# front_gap_sensor.net
KiCad netlist of a schematic drawn in EAGLE
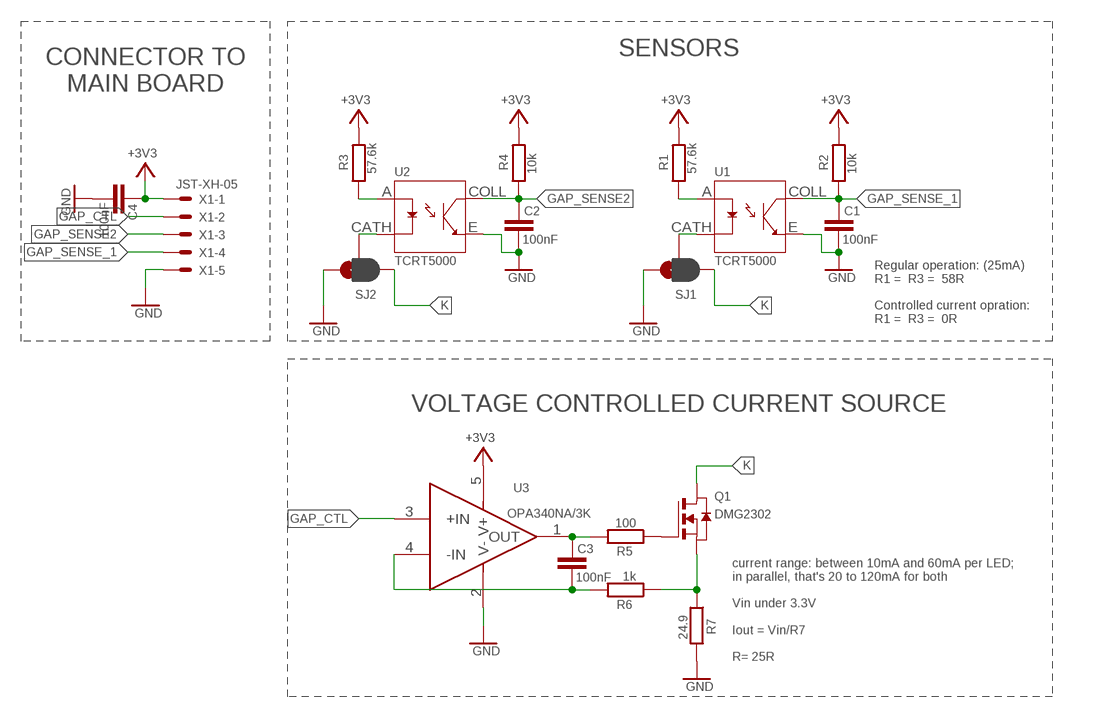
[diagram p0: schematic, sheet 1]

(export (version "E")
  (design (tool "Eeschema 10.0.6"))
  (components
    (comp (ref "C1")
      (value "100nF")
      (footprint "eagle-import:C0402")
      (libsource (lib "eagle-import") (part "C-EUC0402"))
    )
    (comp (ref "C2")
      (value "100nF")
      (footprint "eagle-import:C0402")
      (libsource (lib "eagle-import") (part "C-EUC0402"))
    )
    (comp (ref "C3")
      (value "100nF")
      (footprint "eagle-import:C0402")
      (libsource (lib "eagle-import") (part "C-EUC0402"))
    )
    (comp (ref "C4")
      (value "100nF")
      (footprint "eagle-import:C0402")
      (libsource (lib "eagle-import") (part "C-EUC0402"))
    )
    (comp (ref "Q1")
      (value "DMG2302")
      (footprint "eagle-import:SOT-23")
      (libsource (lib "eagle-import") (part "NMOS-SOT23"))
    )
    (comp (ref "R1")
      (value "57.6k")
      (footprint "eagle-import:R0402")
      (libsource (lib "eagle-import") (part "R-EU_R0402"))
    )
    (comp (ref "R2")
      (value "10k")
      (footprint "eagle-import:R0402")
      (libsource (lib "eagle-import") (part "R-EU_R0402"))
    )
    (comp (ref "R3")
      (value "57.6k")
      (footprint "eagle-import:R0402")
      (libsource (lib "eagle-import") (part "R-EU_R0402"))
    )
    (comp (ref "R4")
      (value "10k")
      (footprint "eagle-import:R0402")
      (libsource (lib "eagle-import") (part "R-EU_R0402"))
    )
    (comp (ref "R5")
      (value "100")
      (footprint "eagle-import:R0402")
      (libsource (lib "eagle-import") (part "R-EU_R0402"))
    )
    (comp (ref "R6")
      (value "1k")
      (footprint "eagle-import:R0402")
      (libsource (lib "eagle-import") (part "R-EU_R0402"))
    )
    (comp (ref "R7")
      (value "24.9")
      (footprint "eagle-import:R0402")
      (libsource (lib "eagle-import") (part "R-EU_R0402"))
    )
    (comp (ref "SJ1")
      (value "SPARKFUN-PASSIVES_JUMPER_PAD-3-1&2_NC_BY_PASTE")
      (footprint "eagle-import:SPARKFUN-PASSIVES_PAD-HUMPER-3-1&2_NC_BY_PASTE_YES_SILK_FULL_BOX")
      (libsource (lib "eagle-import") (part "SPARKFUN-PASSIVES_JUMPER_PAD-3-1&2_NC_BY_PASTE"))
    )
    (comp (ref "SJ2")
      (value "SPARKFUN-PASSIVES_JUMPER_PAD-3-1&2_NC_BY_PASTE")
      (footprint "eagle-import:SPARKFUN-PASSIVES_PAD-HUMPER-3-1&2_NC_BY_PASTE_YES_SILK_FULL_BOX")
      (libsource (lib "eagle-import") (part "SPARKFUN-PASSIVES_JUMPER_PAD-3-1&2_NC_BY_PASTE"))
    )
    (comp (ref "U1")
      (value "TCRT5000")
      (footprint "eagle-import:OPTO_TCRT5000")
      (fields (field (name "MF") "Vishay"))
      (libsource (lib "eagle-import") (part "TCRT5000"))
    )
    (comp (ref "U2")
      (value "TCRT5000")
      (footprint "eagle-import:OPTO_TCRT5000")
      (fields (field (name "MF") "Vishay"))
      (libsource (lib "eagle-import") (part "TCRT5000"))
    )
    (comp (ref "U3")
      (value "OPA340NA/3K")
      (footprint "eagle-import:SOT95P280X145-5N")
      (fields (field (name "MF") "Texas Instruments"))
      (libsource (lib "eagle-import") (part "OPA340NA/3K"))
    )
    (comp (ref "X1")
      (value "JST-XH-05")
      (footprint "eagle-import:JST-XH-05-PACKAGE-ROUND-PAD")
      (libsource (lib "eagle-import") (part "JST-XH-05-PIN-ROUND-PAD"))
    )
  )
  (nets
    (net (code "1") (name "+3V3") (class "Default")
      (node (ref "C4") (pin "2") (pinfunction "2_2") (pintype "passive"))
      (node (ref "R1") (pin "2") (pinfunction "2_2") (pintype "passive"))
      (node (ref "R2") (pin "2") (pinfunction "2_2") (pintype "passive"))
      (node (ref "R3") (pin "2") (pinfunction "2_2") (pintype "passive"))
      (node (ref "R4") (pin "2") (pinfunction "2_2") (pintype "passive"))
      (node (ref "U3") (pin "5") (pinfunction "V+_5") (pintype "power_in"))
      (node (ref "X1") (pin "1") (pinfunction "S_1") (pintype "passive"))
    )
    (net (code "2") (name "GAP_CTL") (class "Default")
      (node (ref "U3") (pin "3") (pinfunction "+IN_3") (pintype "input"))
      (node (ref "X1") (pin "2") (pinfunction "S_2") (pintype "passive"))
    )
    (net (code "3") (name "GAP_SENSE2") (class "Default")
      (node (ref "C2") (pin "2") (pinfunction "2_2") (pintype "passive"))
      (node (ref "R4") (pin "1") (pinfunction "1_1") (pintype "passive"))
      (node (ref "U2") (pin "COLL") (pinfunction "COLL_COLL") (pintype "passive"))
      (node (ref "X1") (pin "3") (pinfunction "S_3") (pintype "passive"))
    )
    (net (code "4") (name "GAP_SENSE_1") (class "Default")
      (node (ref "C1") (pin "2") (pinfunction "2_2") (pintype "passive"))
      (node (ref "R2") (pin "1") (pinfunction "1_1") (pintype "passive"))
      (node (ref "U1") (pin "COLL") (pinfunction "COLL_COLL") (pintype "passive"))
      (node (ref "X1") (pin "4") (pinfunction "S_4") (pintype "passive"))
    )
    (net (code "5") (name "GND") (class "Default")
      (node (ref "C1") (pin "1") (pinfunction "1_1") (pintype "passive"))
      (node (ref "C2") (pin "1") (pinfunction "1_1") (pintype "passive"))
      (node (ref "C4") (pin "1") (pinfunction "1_1") (pintype "passive"))
      (node (ref "R7") (pin "2") (pinfunction "2_2") (pintype "passive"))
      (node (ref "SJ1") (pin "3") (pinfunction "3_3") (pintype "passive"))
      (node (ref "SJ2") (pin "3") (pinfunction "3_3") (pintype "passive"))
      (node (ref "U1") (pin "E") (pinfunction "E_E") (pintype "passive"))
      (node (ref "U2") (pin "E") (pinfunction "E_E") (pintype "passive"))
      (node (ref "U3") (pin "2") (pinfunction "V-_2") (pintype "power_in"))
      (node (ref "X1") (pin "5") (pinfunction "S_5") (pintype "passive"))
    )
    (net (code "6") (name "K") (class "Default")
      (node (ref "Q1") (pin "D") (pinfunction "D_D") (pintype "passive"))
      (node (ref "SJ1") (pin "1") (pinfunction "1_1") (pintype "passive"))
      (node (ref "SJ2") (pin "1") (pinfunction "1_1") (pintype "passive"))
    )
    (net (code "7") (name "Net-(Q1-PadG)") (class "Default")
      (node (ref "Q1") (pin "G") (pinfunction "G_G") (pintype "passive"))
      (node (ref "R5") (pin "1") (pinfunction "1_1") (pintype "passive"))
    )
    (net (code "8") (name "Net-(Q1-PadS)") (class "Default")
      (node (ref "Q1") (pin "S") (pinfunction "S_S") (pintype "passive"))
      (node (ref "R6") (pin "1") (pinfunction "1_1") (pintype "passive"))
      (node (ref "R7") (pin "1") (pinfunction "1_1") (pintype "passive"))
    )
    (net (code "9") (name "Net-(R1-Pad1)") (class "Default")
      (node (ref "R1") (pin "1") (pinfunction "1_1") (pintype "passive"))
      (node (ref "U1") (pin "A") (pinfunction "A_A") (pintype "passive"))
    )
    (net (code "10") (name "Net-(R3-Pad1)") (class "Default")
      (node (ref "R3") (pin "1") (pinfunction "1_1") (pintype "passive"))
      (node (ref "U2") (pin "A") (pinfunction "A_A") (pintype "passive"))
    )
    (net (code "11") (name "Net-(SJ1-Pad2)") (class "Default")
      (node (ref "SJ1") (pin "2") (pinfunction "2_2") (pintype "passive"))
      (node (ref "U1") (pin "CATH") (pinfunction "CATH_CATH") (pintype "passive"))
    )
    (net (code "12") (name "Net-(SJ2-Pad2)") (class "Default")
      (node (ref "SJ2") (pin "2") (pinfunction "2_2") (pintype "passive"))
      (node (ref "U2") (pin "CATH") (pinfunction "CATH_CATH") (pintype "passive"))
    )
    (net (code "13") (name "Net-(U3--IN)") (class "Default")
      (node (ref "C3") (pin "1") (pinfunction "1_1") (pintype "passive"))
      (node (ref "R6") (pin "2") (pinfunction "2_2") (pintype "passive"))
      (node (ref "U3") (pin "4") (pinfunction "-IN_4") (pintype "input"))
    )
    (net (code "14") (name "Net-(U3-OUT)") (class "Default")
      (node (ref "C3") (pin "2") (pinfunction "2_2") (pintype "passive"))
      (node (ref "R5") (pin "2") (pinfunction "2_2") (pintype "passive"))
      (node (ref "U3") (pin "1") (pinfunction "OUT_1") (pintype "output"))
    )
  )
)
